# Impalyzer.net
KiCad netlist of a schematic drawn in EAGLE
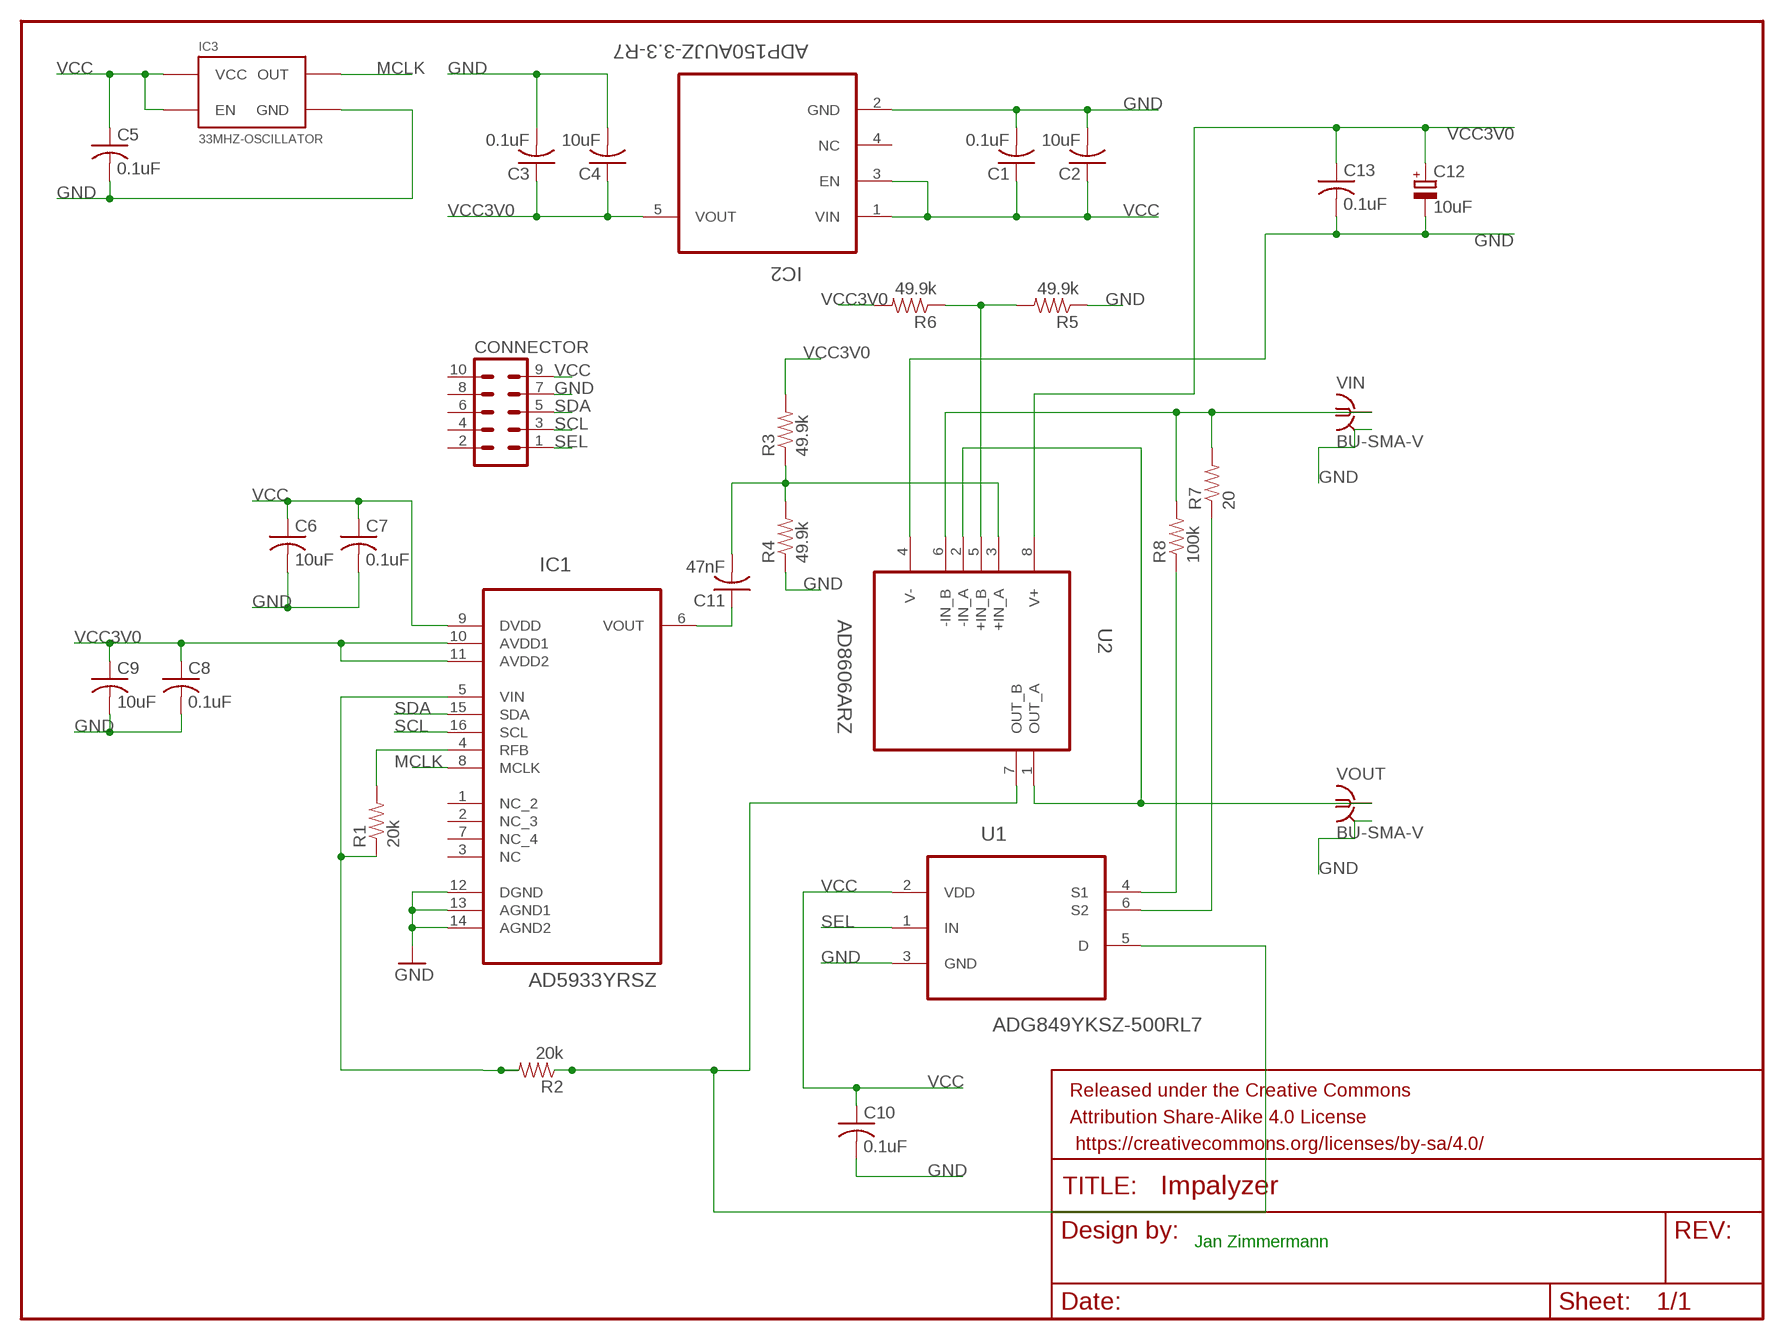
[diagram p0: schematic, sheet 1]

(export (version "E")
  (design (tool "Eeschema 10.0.6"))
  (components
    (comp (ref "C1")
      (value "0.1uF")
      (footprint "eagle-import:C0402")
      (libsource (lib "eagle-import") (part "C-USC0402"))
    )
    (comp (ref "C2")
      (value "10uF")
      (footprint "eagle-import:C0402")
      (libsource (lib "eagle-import") (part "C-USC0402"))
    )
    (comp (ref "C3")
      (value "0.1uF")
      (footprint "eagle-import:C0402")
      (libsource (lib "eagle-import") (part "C-USC0402"))
    )
    (comp (ref "C4")
      (value "10uF")
      (footprint "eagle-import:C0402")
      (libsource (lib "eagle-import") (part "C-USC0402"))
    )
    (comp (ref "C5")
      (value "0.1uF")
      (footprint "eagle-import:C0402")
      (libsource (lib "eagle-import") (part "C-USC0402"))
    )
    (comp (ref "C6")
      (value "10uF")
      (footprint "eagle-import:C0402")
      (libsource (lib "eagle-import") (part "C-USC0402"))
    )
    (comp (ref "C7")
      (value "0.1uF")
      (footprint "eagle-import:C0402")
      (libsource (lib "eagle-import") (part "C-USC0402"))
    )
    (comp (ref "C8")
      (value "0.1uF")
      (footprint "eagle-import:C0402")
      (libsource (lib "eagle-import") (part "C-USC0402"))
    )
    (comp (ref "C9")
      (value "10uF")
      (footprint "eagle-import:C0402")
      (libsource (lib "eagle-import") (part "C-USC0402"))
    )
    (comp (ref "C10")
      (value "0.1uF")
      (footprint "eagle-import:C0402")
      (libsource (lib "eagle-import") (part "C-USC0402"))
    )
    (comp (ref "C11")
      (value "47nF")
      (footprint "eagle-import:C0402")
      (libsource (lib "eagle-import") (part "C-USC0402"))
    )
    (comp (ref "C12")
      (value "10uF")
      (footprint "eagle-import:A_3216-18W")
      (libsource (lib "eagle-import") (part "CPOL-EUA/3216-18W"))
    )
    (comp (ref "C13")
      (value "0.1uF")
      (footprint "eagle-import:C0402")
      (libsource (lib "eagle-import") (part "C-USC0402"))
    )
    (comp (ref "CONNECTOR")
      (value "MA05-2")
      (footprint "eagle-import:MA05-2")
      (libsource (lib "eagle-import") (part "MA05-2"))
    )
    (comp (ref "FRAME1")
      (value "FRAME-LETTERNO_PACKAGE")
      (footprint "eagle-import:DUMMY")
      (fields (field (name "DESIGNER") "Nobody"))
      (libsource (lib "eagle-import") (part "FRAME-LETTERNO_PACKAGE"))
    )
    (comp (ref "IC1")
      (value "AD5933YRSZ")
      (footprint "eagle-import:SOP65P640X120-16N")
      (libsource (lib "eagle-import") (part "AD5933YRSZ"))
    )
    (comp (ref "IC2")
      (value "ADP150AUJZ-3.3-R7")
      (footprint "eagle-import:SOT95P280X100-5N")
      (libsource (lib "eagle-import") (part "ADP150AUJZ-3.3-R7"))
    )
    (comp (ref "IC3")
      (value "33MHZ-OSCILLATOR")
      (footprint "eagle-import:CRYSTAL-OSC-SMD-5X3.2")
      (libsource (lib "eagle-import") (part "33MHZ-OSCILLATOR"))
    )
    (comp (ref "R1")
      (value "20k")
      (footprint "eagle-import:0603-RES")
      (libsource (lib "eagle-import") (part "RESISTOR0603"))
    )
    (comp (ref "R2")
      (value "20k")
      (footprint "eagle-import:0603-RES")
      (libsource (lib "eagle-import") (part "RESISTOR0603"))
    )
    (comp (ref "R3")
      (value "49.9k")
      (footprint "eagle-import:0603-RES")
      (libsource (lib "eagle-import") (part "RESISTOR0603"))
    )
    (comp (ref "R4")
      (value "49.9k")
      (footprint "eagle-import:0603-RES")
      (libsource (lib "eagle-import") (part "RESISTOR0603"))
    )
    (comp (ref "R5")
      (value "49.9k")
      (footprint "eagle-import:0603-RES")
      (libsource (lib "eagle-import") (part "RESISTOR0603"))
    )
    (comp (ref "R6")
      (value "49.9k")
      (footprint "eagle-import:0603-RES")
      (libsource (lib "eagle-import") (part "RESISTOR0603"))
    )
    (comp (ref "R7")
      (value "20")
      (footprint "eagle-import:R2010")
      (libsource (lib "eagle-import") (part "RESISTOR2010"))
    )
    (comp (ref "R8")
      (value "100k")
      (footprint "eagle-import:0603-RES")
      (libsource (lib "eagle-import") (part "RESISTOR0603"))
    )
    (comp (ref "U1")
      (value "ADG849YKSZ-500RL7")
      (footprint "eagle-import:SOT65P210X110-6N")
      (libsource (lib "eagle-import") (part "ADG849YKSZ-500RL7"))
    )
    (comp (ref "U2")
      (value "AD8606ARZ")
      (footprint "eagle-import:SOIC127P600X175-8N")
      (libsource (lib "eagle-import") (part "AD8606ARZ"))
    )
    (comp (ref "VIN")
      (value "BU-SMA-V")
      (footprint "eagle-import:BU-SMA-V")
      (libsource (lib "eagle-import") (part "BU-SMA-V"))
    )
    (comp (ref "VOUT")
      (value "BU-SMA-V")
      (footprint "eagle-import:BU-SMA-V")
      (libsource (lib "eagle-import") (part "BU-SMA-V"))
    )
  )
  (nets
    (net (code "1") (name "/MCLK") (class "Default")
      (node (ref "IC1") (pin "8") (pinfunction "MCLK_8") (pintype "input"))
      (node (ref "IC3") (pin "3") (pinfunction "OUT_3") (pintype "bidirectional"))
    )
    (net (code "2") (name "/SCL") (class "Default")
      (node (ref "CONNECTOR") (pin "3") (pinfunction "3_3") (pintype "passive"))
      (node (ref "IC1") (pin "16") (pinfunction "SCL_16") (pintype "input"))
    )
    (net (code "3") (name "/SDA") (class "Default")
      (node (ref "CONNECTOR") (pin "5") (pinfunction "5_5") (pintype "passive"))
      (node (ref "IC1") (pin "15") (pinfunction "SDA_15") (pintype "bidirectional"))
    )
    (net (code "4") (name "/SEL") (class "Default")
      (node (ref "CONNECTOR") (pin "1") (pinfunction "1_1") (pintype "passive"))
      (node (ref "U1") (pin "1") (pinfunction "IN_1") (pintype "input"))
    )
    (net (code "5") (name "/VCC") (class "Default")
      (node (ref "C1") (pin "1") (pinfunction "1_1") (pintype "passive"))
      (node (ref "C10") (pin "1") (pinfunction "1_1") (pintype "passive"))
      (node (ref "C2") (pin "1") (pinfunction "1_1") (pintype "passive"))
      (node (ref "C5") (pin "1") (pinfunction "1_1") (pintype "passive"))
      (node (ref "C6") (pin "1") (pinfunction "1_1") (pintype "passive"))
      (node (ref "C7") (pin "1") (pinfunction "1_1") (pintype "passive"))
      (node (ref "CONNECTOR") (pin "9") (pinfunction "9_9") (pintype "passive"))
      (node (ref "IC1") (pin "9") (pinfunction "DVDD_9") (pintype "power_in"))
      (node (ref "IC2") (pin "1") (pinfunction "VIN_1") (pintype "power_in"))
      (node (ref "IC2") (pin "3") (pinfunction "EN_3") (pintype "input"))
      (node (ref "IC3") (pin "1") (pinfunction "EN_1") (pintype "bidirectional"))
      (node (ref "IC3") (pin "4") (pinfunction "VCC_4") (pintype "bidirectional"))
      (node (ref "U1") (pin "2") (pinfunction "VDD_2") (pintype "power_in"))
    )
    (net (code "6") (name "/VCC3V0") (class "Default")
      (node (ref "C12") (pin "+") (pinfunction "+_+") (pintype "passive"))
      (node (ref "C13") (pin "1") (pinfunction "1_1") (pintype "passive"))
      (node (ref "C3") (pin "1") (pinfunction "1_1") (pintype "passive"))
      (node (ref "C4") (pin "1") (pinfunction "1_1") (pintype "passive"))
      (node (ref "C8") (pin "1") (pinfunction "1_1") (pintype "passive"))
      (node (ref "C9") (pin "1") (pinfunction "1_1") (pintype "passive"))
      (node (ref "IC1") (pin "10") (pinfunction "AVDD1_10") (pintype "power_in"))
      (node (ref "IC1") (pin "11") (pinfunction "AVDD2_11") (pintype "power_in"))
      (node (ref "IC2") (pin "5") (pinfunction "VOUT_5") (pintype "output"))
      (node (ref "R3") (pin "2") (pinfunction "2_2") (pintype "passive"))
      (node (ref "R6") (pin "2") (pinfunction "2_2") (pintype "passive"))
      (node (ref "U2") (pin "8") (pinfunction "V+_8") (pintype "power_in"))
    )
    (net (code "7") (name "GND") (class "Default")
      (node (ref "C1") (pin "2") (pinfunction "2_2") (pintype "passive"))
      (node (ref "C10") (pin "2") (pinfunction "2_2") (pintype "passive"))
      (node (ref "C12") (pin "-") (pinfunction "-_-") (pintype "passive"))
      (node (ref "C13") (pin "2") (pinfunction "2_2") (pintype "passive"))
      (node (ref "C2") (pin "2") (pinfunction "2_2") (pintype "passive"))
      (node (ref "C3") (pin "2") (pinfunction "2_2") (pintype "passive"))
      (node (ref "C4") (pin "2") (pinfunction "2_2") (pintype "passive"))
      (node (ref "C5") (pin "2") (pinfunction "2_2") (pintype "passive"))
      (node (ref "C6") (pin "2") (pinfunction "2_2") (pintype "passive"))
      (node (ref "C7") (pin "2") (pinfunction "2_2") (pintype "passive"))
      (node (ref "C8") (pin "2") (pinfunction "2_2") (pintype "passive"))
      (node (ref "C9") (pin "2") (pinfunction "2_2") (pintype "passive"))
      (node (ref "CONNECTOR") (pin "7") (pinfunction "7_7") (pintype "passive"))
      (node (ref "IC1") (pin "12") (pinfunction "DGND_12") (pintype "passive"))
      (node (ref "IC1") (pin "13") (pinfunction "AGND1_13") (pintype "passive"))
      (node (ref "IC1") (pin "14") (pinfunction "AGND2_14") (pintype "passive"))
      (node (ref "IC2") (pin "2") (pinfunction "GND_2") (pintype "passive"))
      (node (ref "IC3") (pin "2") (pinfunction "GND_2") (pintype "bidirectional"))
      (node (ref "R4") (pin "1") (pinfunction "1_1") (pintype "passive"))
      (node (ref "R5") (pin "1") (pinfunction "1_1") (pintype "passive"))
      (node (ref "U1") (pin "3") (pinfunction "GND_3") (pintype "passive"))
      (node (ref "U2") (pin "4") (pinfunction "V-_4") (pintype "power_in"))
      (node (ref "VIN") (pin "2") (pinfunction "2_2") (pintype "passive"))
      (node (ref "VIN") (pin "3") (pinfunction "2_3") (pintype "passive"))
      (node (ref "VIN") (pin "4") (pinfunction "2_4") (pintype "passive"))
      (node (ref "VIN") (pin "5") (pinfunction "2_5") (pintype "passive"))
      (node (ref "VOUT") (pin "2") (pinfunction "2_2") (pintype "passive"))
      (node (ref "VOUT") (pin "3") (pinfunction "2_3") (pintype "passive"))
      (node (ref "VOUT") (pin "4") (pinfunction "2_4") (pintype "passive"))
      (node (ref "VOUT") (pin "5") (pinfunction "2_5") (pintype "passive"))
    )
    (net (code "8") (name "Net-(IC1-RFB)") (class "Default")
      (node (ref "IC1") (pin "4") (pinfunction "RFB_4") (pintype "input"))
      (node (ref "R1") (pin "2") (pinfunction "2_2") (pintype "passive"))
    )
    (net (code "9") (name "Net-(IC1-VIN)") (class "Default")
      (node (ref "IC1") (pin "5") (pinfunction "VIN_5") (pintype "input"))
      (node (ref "R1") (pin "1") (pinfunction "1_1") (pintype "passive"))
      (node (ref "R2") (pin "2") (pinfunction "2_2") (pintype "passive"))
    )
    (net (code "10") (name "Net-(IC1-VOUT)") (class "Default")
      (node (ref "C11") (pin "1") (pinfunction "1_1") (pintype "passive"))
      (node (ref "IC1") (pin "6") (pinfunction "VOUT_6") (pintype "output"))
    )
    (net (code "11") (name "Net-(U1-D)") (class "Default")
      (node (ref "R2") (pin "1") (pinfunction "1_1") (pintype "passive"))
      (node (ref "U1") (pin "5") (pinfunction "D_5") (pintype "bidirectional"))
      (node (ref "U2") (pin "7") (pinfunction "OUT_B_7") (pintype "output"))
    )
    (net (code "12") (name "Net-(U1-S1)") (class "Default")
      (node (ref "R8") (pin "1") (pinfunction "1_1") (pintype "passive"))
      (node (ref "U1") (pin "4") (pinfunction "S1_4") (pintype "bidirectional"))
    )
    (net (code "13") (name "Net-(U1-S2)") (class "Default")
      (node (ref "R7") (pin "1") (pinfunction "1_1") (pintype "passive"))
      (node (ref "U1") (pin "6") (pinfunction "S2_6") (pintype "bidirectional"))
    )
    (net (code "14") (name "Net-(U2-+IN_A)") (class "Default")
      (node (ref "C11") (pin "2") (pinfunction "2_2") (pintype "passive"))
      (node (ref "R3") (pin "1") (pinfunction "1_1") (pintype "passive"))
      (node (ref "R4") (pin "2") (pinfunction "2_2") (pintype "passive"))
      (node (ref "U2") (pin "3") (pinfunction "+IN_A_3") (pintype "input"))
    )
    (net (code "15") (name "Net-(U2-+IN_B)") (class "Default")
      (node (ref "R5") (pin "2") (pinfunction "2_2") (pintype "passive"))
      (node (ref "R6") (pin "1") (pinfunction "1_1") (pintype "passive"))
      (node (ref "U2") (pin "5") (pinfunction "+IN_B_5") (pintype "input"))
    )
    (net (code "16") (name "Net-(U2--IN_A)") (class "Default")
      (node (ref "U2") (pin "1") (pinfunction "OUT_A_1") (pintype "output"))
      (node (ref "U2") (pin "2") (pinfunction "-IN_A_2") (pintype "input"))
      (node (ref "VOUT") (pin "1") (pinfunction "1_1") (pintype "passive"))
    )
    (net (code "17") (name "Net-(U2--IN_B)") (class "Default")
      (node (ref "R7") (pin "2") (pinfunction "2_2") (pintype "passive"))
      (node (ref "R8") (pin "2") (pinfunction "2_2") (pintype "passive"))
      (node (ref "U2") (pin "6") (pinfunction "-IN_B_6") (pintype "input"))
      (node (ref "VIN") (pin "1") (pinfunction "1_1") (pintype "passive"))
    )
    (net (code "18") (name "unconnected-(CONNECTOR-Pad2)") (class "Default")
      (node (ref "CONNECTOR") (pin "2") (pinfunction "2_2") (pintype "passive"))
    )
    (net (code "19") (name "unconnected-(CONNECTOR-Pad4)") (class "Default")
      (node (ref "CONNECTOR") (pin "4") (pinfunction "4_4") (pintype "passive"))
    )
    (net (code "20") (name "unconnected-(CONNECTOR-Pad6)") (class "Default")
      (node (ref "CONNECTOR") (pin "6") (pinfunction "6_6") (pintype "passive"))
    )
    (net (code "21") (name "unconnected-(CONNECTOR-Pad8)") (class "Default")
      (node (ref "CONNECTOR") (pin "8") (pinfunction "8_8") (pintype "passive"))
    )
    (net (code "22") (name "unconnected-(CONNECTOR-Pad10)") (class "Default")
      (node (ref "CONNECTOR") (pin "10") (pinfunction "10_10") (pintype "passive"))
    )
    (net (code "23") (name "unconnected-(IC1-NC-Pad3)") (class "Default")
      (node (ref "IC1") (pin "3") (pinfunction "NC_3") (pintype "no_connect"))
    )
    (net (code "24") (name "unconnected-(IC1-NC_2-Pad1)") (class "Default")
      (node (ref "IC1") (pin "1") (pinfunction "NC_2_1") (pintype "no_connect"))
    )
    (net (code "25") (name "unconnected-(IC1-NC_3-Pad2)") (class "Default")
      (node (ref "IC1") (pin "2") (pinfunction "NC_3_2") (pintype "no_connect"))
    )
    (net (code "26") (name "unconnected-(IC1-NC_4-Pad7)") (class "Default")
      (node (ref "IC1") (pin "7") (pinfunction "NC_4_7") (pintype "no_connect"))
    )
    (net (code "27") (name "unconnected-(IC2-NC-Pad4)") (class "Default")
      (node (ref "IC2") (pin "4") (pinfunction "NC_4") (pintype "no_connect"))
    )
  )
)
